# MIRA050CSP-Sheet1.net
KiCad netlist of a schematic drawn in Altium Designer
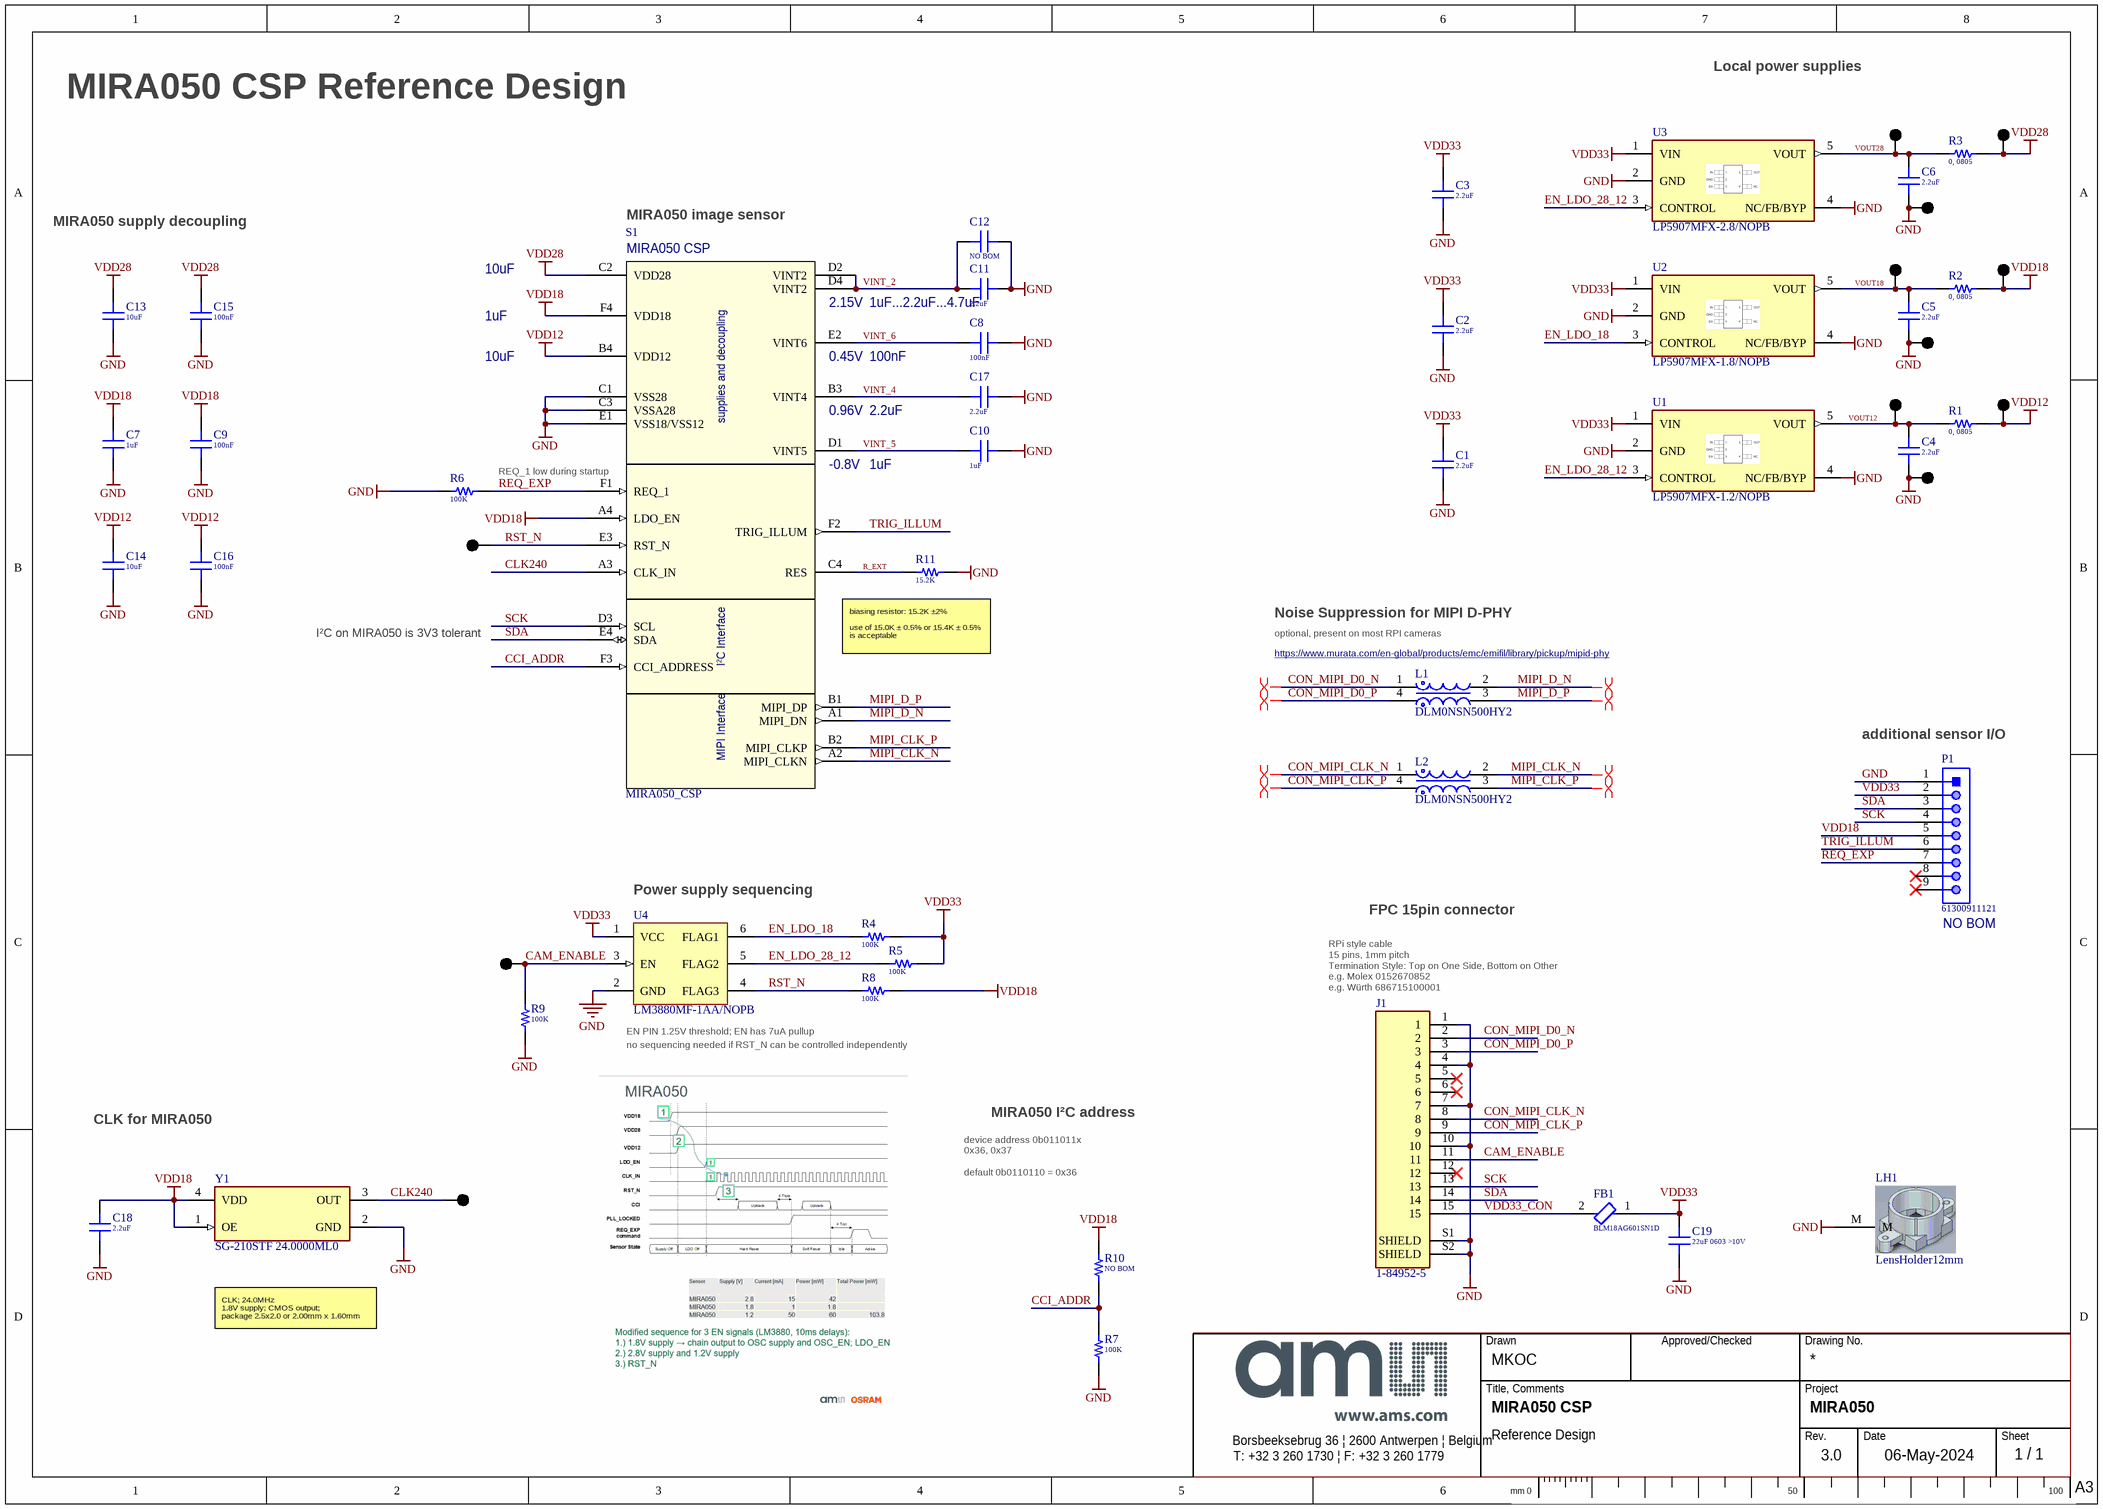
[diagram p0: MIRA050CSP-Sheet1.SchDoc]

(export (version "E")
  (design (tool "Eeschema 10.0.6"))
  (components
    (comp (ref "C1")
      (value "2.2uF")
      (footprint "CAPC0402_BEMA")
      (description "SMT Capacitor")
      (fields (field (name "PART NUMBER") "GRM155R61E225ME15D"))
      (libsource (lib "passives") (part "Capacitor"))
    )
    (comp (ref "C2")
      (value "2.2uF")
      (footprint "CAPC0402_BEMA")
      (description "SMT Capacitor")
      (fields (field (name "PART NUMBER") "GRM155R61E225ME15D"))
      (libsource (lib "passives") (part "Capacitor"))
    )
    (comp (ref "C3")
      (value "2.2uF")
      (footprint "CAPC0402_BEMA")
      (description "SMT Capacitor")
      (fields (field (name "PART NUMBER") "GRM155R61E225ME15D"))
      (libsource (lib "passives") (part "Capacitor"))
    )
    (comp (ref "C4")
      (value "2.2uF")
      (footprint "CAPC0402_BEMA")
      (description "SMT Capacitor")
      (fields (field (name "PART NUMBER") "GRM155R61E225ME15D"))
      (libsource (lib "passives") (part "Capacitor"))
    )
    (comp (ref "C5")
      (value "2.2uF")
      (footprint "CAPC0402_BEMA")
      (description "SMT Capacitor")
      (fields (field (name "PART NUMBER") "GRM155R61E225ME15D"))
      (libsource (lib "passives") (part "Capacitor"))
    )
    (comp (ref "C6")
      (value "2.2uF")
      (footprint "CAPC0402_BEMA")
      (description "SMT Capacitor")
      (fields (field (name "PART NUMBER") "GRM155R61E225ME15D"))
      (libsource (lib "passives") (part "Capacitor"))
    )
    (comp (ref "C7")
      (value "1uF")
      (footprint "CAPC0402_BEMA")
      (description "SMT Capacitor")
      (fields (field (name "PART NUMBER") "GRM155Z71A105KE01"))
      (libsource (lib "passives") (part "Capacitor"))
    )
    (comp (ref "C8")
      (value "100nF")
      (footprint "CAPC0402_BEMA")
      (description "SMT Capacitor")
      (fields (field (name "PART NUMBER") "GRM155R71E104KE14J"))
      (libsource (lib "passives") (part "Capacitor"))
    )
    (comp (ref "C9")
      (value "100nF")
      (footprint "CAPC0402_BEMA")
      (description "SMT Capacitor")
      (fields (field (name "PART NUMBER") "GRM155R71E104KE14J"))
      (libsource (lib "passives") (part "Capacitor"))
    )
    (comp (ref "C10")
      (value "1uF")
      (footprint "CAPC0402_BEMA")
      (description "SMT Capacitor")
      (fields (field (name "PART NUMBER") "GRM155Z71A105KE01"))
      (libsource (lib "passives") (part "Capacitor"))
    )
    (comp (ref "C11")
      (value "2.2uF")
      (footprint "CAPC0402_N")
      (description "SMT Capacitor")
      (fields (field (name "PART NUMBER") "GRM155R61E225ME15D"))
      (libsource (lib "passives") (part "Capacitor"))
    )
    (comp (ref "C12")
      (value "NO BOM")
      (footprint "CAPC0402_N")
      (description "SMT Capacitor")
      (libsource (lib "passives") (part "Capacitor"))
    )
    (comp (ref "C13")
      (value "10uF")
      (footprint "CAPC0402_BEMA")
      (description "SMT Capacitor")
      (fields (field (name "PART NUMBER") "GRM155R60J106ME15D"))
      (libsource (lib "passives") (part "Capacitor"))
    )
    (comp (ref "C14")
      (value "10uF")
      (footprint "CAPC0402_BEMA")
      (description "SMT Capacitor")
      (fields (field (name "PART NUMBER") "GRM155R60J106ME15D"))
      (libsource (lib "passives") (part "Capacitor"))
    )
    (comp (ref "C15")
      (value "100nF")
      (footprint "CAPC0402_BEMA")
      (description "SMT Capacitor")
      (fields (field (name "PART NUMBER") "GRM155R71E104KE14J"))
      (libsource (lib "passives") (part "Capacitor"))
    )
    (comp (ref "C16")
      (value "100nF")
      (footprint "CAPC0402_BEMA")
      (description "SMT Capacitor")
      (fields (field (name "PART NUMBER") "GRM155R71E104KE14J"))
      (libsource (lib "passives") (part "Capacitor"))
    )
    (comp (ref "C17")
      (value "2.2uF")
      (footprint "CAPC0402_BEMA")
      (description "SMT Capacitor")
      (fields (field (name "PART NUMBER") "GRM155R61E225ME15D"))
      (libsource (lib "passives") (part "Capacitor"))
    )
    (comp (ref "C18")
      (value "2.2uF")
      (footprint "CAPC0402_BEMA")
      (description "SMT Capacitor")
      (fields (field (name "PART NUMBER") "GRM155R61E225ME15D"))
      (libsource (lib "passives") (part "Capacitor"))
    )
    (comp (ref "C19")
      (value "22uF 0603 >10V")
      (footprint "CAPC0603_BEMA")
      (description "SMT Capacitor")
      (fields (field (name "PART NUMBER") "GRM187R61A226ME15D"))
      (libsource (lib "passives") (part "Capacitor"))
    )
    (comp (ref "FB1")
      (value "BLM18AG601SN1D")
      (footprint "FP-BLM18-0_15-t0_8-IPC_B")
      (description "Chip Ferrite Bead, 0603, 600Ω @ 100MHz, 0.38Ω, 25%, 500mA")
      (fields (field (name "TOLERANCE") "25%"))
      (libsource (lib "MIRA050CSP") (part "CMP-0686-00436-3"))
    )
    (comp (ref "J1")
      (value "1-84952-5")
      (footprint "TE_1-84952-5")
      (description "Conn FPC Connector SKT 15 POS 1mm Solder RA SMD T/R")
      (libsource (lib "MIRA220CSP") (part "1-84952-5"))
    )
    (comp (ref "L1")
      (value "DLM0NSN500HY2")
      (footprint "FP-DLM0N-MFG")
      (description "Common Mode Choke 50Ohm 100mA 4-Pin 03025 Paper T/R")
      (fields
        (field (name "MANUFACTURER") "Murata")
        (field (name "MANUFACTURER PART NUMBER") "DLM0NSN500HY2D")
      )
      (libsource (lib "MIRA050CSP") (part "CMP-2000-06161-2_1"))
    )
    (comp (ref "L2")
      (value "DLM0NSN500HY2")
      (footprint "FP-DLM0N-MFG")
      (description "Common Mode Choke 50Ohm 100mA 4-Pin 03025 Paper T/R")
      (fields
        (field (name "MANUFACTURER") "Murata")
        (field (name "MANUFACTURER PART NUMBER") "DLM0NSN500HY2D")
      )
      (libsource (lib "MIRA050CSP") (part "CMP-2000-06161-2_1"))
    )
    (comp (ref "LH1")
      (value "LensHolder12mm")
      (footprint "LensHolder12mmSmount")
      (libsource (lib "misc_components") (part "LensHolder12mm"))
    )
    (comp (ref "P1")
      (value "61300911121")
      (footprint "61300911121")
      (description "THT Vertical Pin Header WR-PHD, Pitch 2.54 mm, Single Row, 9 pins")
      (fields (field (name "MANUFACTURER") "Wurth Elektronik") (field (name "PUBLISHER") "WurthElektronik"))
      (libsource (lib "MIRA050CSP") (part "CMP-1502-01080-1"))
    )
    (comp (ref "R1")
      (value "0, 0805")
      (footprint "RESC0805_BEMA")
      (description "SMT Resistor")
      (fields (field (name "PART NUMBER") "0, 0805, generic"))
      (libsource (lib "passives") (part "Resistor"))
    )
    (comp (ref "R2")
      (value "0, 0805")
      (footprint "RESC0805_BEMA")
      (description "SMT Resistor")
      (fields (field (name "PART NUMBER") "0, 0805, generic"))
      (libsource (lib "passives") (part "Resistor"))
    )
    (comp (ref "R3")
      (value "0, 0805")
      (footprint "RESC0805_BEMA")
      (description "SMT Resistor")
      (fields (field (name "PART NUMBER") "0, 0805, generic"))
      (libsource (lib "passives") (part "Resistor"))
    )
    (comp (ref "R4")
      (value "100K")
      (footprint "RESC0402_BEMA")
      (description "SMT Resistor")
      (fields (field (name "PART NUMBER") "100K 0402, generic"))
      (libsource (lib "passives") (part "Resistor"))
    )
    (comp (ref "R5")
      (value "100K")
      (footprint "RESC0402_BEMA")
      (description "SMT Resistor")
      (fields (field (name "PART NUMBER") "100K 0402, generic"))
      (libsource (lib "passives") (part "Resistor"))
    )
    (comp (ref "R6")
      (value "100K")
      (footprint "RESC0402_BEMA")
      (description "SMT Resistor")
      (fields (field (name "PART NUMBER") "100K 0402, generic"))
      (libsource (lib "passives") (part "Resistor"))
    )
    (comp (ref "R7")
      (value "100K")
      (footprint "RESC0402_BEMA")
      (description "SMT Resistor")
      (fields (field (name "PART NUMBER") "100K 0402, generic"))
      (libsource (lib "passives") (part "Resistor"))
    )
    (comp (ref "R8")
      (value "100K")
      (footprint "RESC0402_BEMA")
      (description "SMT Resistor")
      (fields (field (name "PART NUMBER") "100K 0402, generic"))
      (libsource (lib "passives") (part "Resistor"))
    )
    (comp (ref "R9")
      (value "100K")
      (footprint "RESC0402_BEMA")
      (description "SMT Resistor")
      (fields (field (name "PART NUMBER") "100K 0402, generic"))
      (libsource (lib "passives") (part "Resistor"))
    )
    (comp (ref "R10")
      (value "NO BOM")
      (footprint "RESC0402_BEMA")
      (description "SMT Resistor")
      (libsource (lib "passives") (part "Resistor"))
    )
    (comp (ref "R11")
      (value "15.2K")
      (footprint "RESC0402_BEMA")
      (description "SMT Resistor")
      (fields (field (name "PART NUMBER") "RN73R1ETTP1522B25"))
      (libsource (lib "passives") (part "Resistor"))
    )
    (comp (ref "S1")
      (value "MIRA050_CSP")
      (footprint "MIRA050CSP:MIRA050CSP")
      (description "AMS-OSRAM MIRA050 CSP, MONO")
      (fields (field (name "PART NUMBER") "Mira050-2QM1WB"))
      (libsource (lib "MIRA050CSP") (part "MIRA050_CSP"))
    )
    (comp (ref "TP1")
      (value "1V8")
      (footprint "misc_components:TP_1mm")
      (description "Test Point, various footprints")
      (libsource (lib "misc_components") (part "TestPoint"))
    )
    (comp (ref "TP2")
      (value "1V2")
      (footprint "misc_components:TP_1mm")
      (description "Test Point, various footprints")
      (libsource (lib "misc_components") (part "TestPoint"))
    )
    (comp (ref "TP3")
      (value "TestPoint")
      (footprint "misc_components:TP_1mm")
      (description "Test Point, various footprints")
      (libsource (lib "misc_components") (part "TestPoint"))
    )
    (comp (ref "TP4")
      (value "TestPoint")
      (footprint "misc_components:TP_1mm")
      (description "Test Point, various footprints")
      (libsource (lib "misc_components") (part "TestPoint"))
    )
    (comp (ref "TP5")
      (value "2V8")
      (footprint "misc_components:TP_1mm")
      (description "Test Point, various footprints")
      (libsource (lib "misc_components") (part "TestPoint"))
    )
    (comp (ref "TP6")
      (value "TestPoint")
      (footprint "misc_components:TP_1mm")
      (description "Test Point, various footprints")
      (libsource (lib "misc_components") (part "TestPoint"))
    )
    (comp (ref "TP7")
      (value "TestPoint")
      (footprint "misc_components:TP_075mm")
      (description "Test Point, various footprints")
      (libsource (lib "misc_components") (part "TestPoint"))
    )
    (comp (ref "TP8")
      (value "TestPoint")
      (footprint "misc_components:TP_075mm")
      (description "Test Point, various footprints")
      (libsource (lib "misc_components") (part "TestPoint"))
    )
    (comp (ref "TP9")
      (value "TestPoint")
      (footprint "misc_components:TP_075mm")
      (description "Test Point, various footprints")
      (libsource (lib "misc_components") (part "TestPoint"))
    )
    (comp (ref "TP10")
      (value "TestPoint")
      (footprint "TP_1mm")
      (description "Test Point, various footprints")
      (libsource (lib "MIRA050CSP") (part "5001"))
    )
    (comp (ref "TP11")
      (value "TestPoint")
      (footprint "TP_1mm")
      (description "Test Point, various footprints")
      (libsource (lib "MIRA050CSP") (part "5001"))
    )
    (comp (ref "TP12")
      (value "TestPoint")
      (footprint "TP_1mm")
      (description "Test Point, various footprints")
      (libsource (lib "MIRA050CSP") (part "5001"))
    )
    (comp (ref "U1")
      (value "LP5907MFX-1.2/NOPB")
      (footprint "misc_components:FP-DBV0005A-MFG")
      (description "IC REG LINEAR fixed Voltage, SOT23-5 / SOT-25 / SC74A package")
      (libsource (lib "misc_components") (part "LDO-STO23-5"))
    )
    (comp (ref "U2")
      (value "LP5907MFX-1.8/NOPB")
      (footprint "misc_components:FP-DBV0005A-MFG")
      (description "IC REG LINEAR fixed Voltage, SOT23-5 / SOT-25 / SC74A package")
      (libsource (lib "misc_components") (part "LDO-STO23-5"))
    )
    (comp (ref "U3")
      (value "LP5907MFX-2.8/NOPB")
      (footprint "misc_components:FP-DBV0005A-MFG")
      (description "IC REG LINEAR fixed Voltage, SOT23-5 / SOT-25 / SC74A package")
      (libsource (lib "misc_components") (part "LDO-STO23-5"))
    )
    (comp (ref "U4")
      (value "LM3880MF-1AA/NOPB")
      (footprint "DBV0006A_N")
      (description "Power Sequencer, 6-pin SOT-23, Pb-Free, 1000 Reel")
      (libsource (lib "MIRA050CSP") (part "CMP-0063-01015-4"))
    )
    (comp (ref "Y1")
      (value "SG-210STF 24.0000ML0")
      (footprint "MIRA050CSP:2.5x2_OSC")
      (description "OSC, 24MHz, 1.8V, CMOS, EN")
      (libsource (lib "MIRA050CSP") (part "OSC"))
    )
  )
  (nets
    (net (code "1") (name "/CAM_ENABLE") (class "Default")
      (node (ref "J1") (pin "11") (pinfunction "11_11") (pintype "passive"))
      (node (ref "R9") (pin "2") (pinfunction "2_2") (pintype "passive"))
      (node (ref "TP12") (pin "1") (pintype "passive"))
      (node (ref "U4") (pin "3") (pinfunction "EN_3") (pintype "input"))
    )
    (net (code "2") (name "/CCI_ADDR") (class "Default")
      (node (ref "R10") (pin "1") (pinfunction "1_1") (pintype "passive"))
      (node (ref "R7") (pin "2") (pinfunction "2_2") (pintype "passive"))
      (node (ref "S1") (pin "F3") (pinfunction "CCI_ADDRESS_F3") (pintype "input"))
    )
    (net (code "3") (name "/CLK240") (class "Default")
      (node (ref "S1") (pin "A3") (pinfunction "CLK_IN_A3") (pintype "input"))
      (node (ref "TP11") (pin "1") (pintype "passive"))
      (node (ref "Y1") (pin "3") (pinfunction "OUT_3") (pintype "passive"))
    )
    (net (code "4") (name "/CON_MIPI_CLK_N") (class "Default")
      (node (ref "J1") (pin "8") (pinfunction "8_8") (pintype "passive"))
      (node (ref "L2") (pin "1") (pinfunction "1_1") (pintype "passive"))
    )
    (net (code "5") (name "/CON_MIPI_CLK_P") (class "Default")
      (node (ref "J1") (pin "9") (pinfunction "9_9") (pintype "passive"))
      (node (ref "L2") (pin "4") (pinfunction "4_4") (pintype "passive"))
    )
    (net (code "6") (name "/CON_MIPI_D0_N") (class "Default")
      (node (ref "J1") (pin "2") (pinfunction "2_2") (pintype "passive"))
      (node (ref "L1") (pin "1") (pinfunction "1_1") (pintype "passive"))
    )
    (net (code "7") (name "/CON_MIPI_D0_P") (class "Default")
      (node (ref "J1") (pin "3") (pinfunction "3_3") (pintype "passive"))
      (node (ref "L1") (pin "4") (pinfunction "4_4") (pintype "passive"))
    )
    (net (code "8") (name "/EN_LDO_18") (class "Default")
      (node (ref "R4") (pin "1") (pinfunction "1_1") (pintype "passive"))
      (node (ref "U2") (pin "3") (pinfunction "CONTROL_3") (pintype "input"))
      (node (ref "U4") (pin "6") (pinfunction "FLAG1_6") (pintype "open_collector"))
    )
    (net (code "9") (name "/EN_LDO_28_12") (class "Default")
      (node (ref "R5") (pin "1") (pinfunction "1_1") (pintype "passive"))
      (node (ref "U1") (pin "3") (pinfunction "CONTROL_3") (pintype "input"))
      (node (ref "U3") (pin "3") (pinfunction "CONTROL_3") (pintype "input"))
      (node (ref "U4") (pin "5") (pinfunction "FLAG2_5") (pintype "open_collector"))
    )
    (net (code "10") (name "/MIPI_CLK_N") (class "Default")
      (node (ref "L2") (pin "2") (pinfunction "2_2") (pintype "passive"))
      (node (ref "S1") (pin "A2") (pinfunction "MIPI_CLKN_A2") (pintype "output"))
    )
    (net (code "11") (name "/MIPI_CLK_P") (class "Default")
      (node (ref "L2") (pin "3") (pinfunction "3_3") (pintype "passive"))
      (node (ref "S1") (pin "B2") (pinfunction "MIPI_CLKP_B2") (pintype "output"))
    )
    (net (code "12") (name "/MIPI_D_N") (class "Default")
      (node (ref "L1") (pin "2") (pinfunction "2_2") (pintype "passive"))
      (node (ref "S1") (pin "A1") (pinfunction "MIPI_DN_A1") (pintype "output"))
    )
    (net (code "13") (name "/MIPI_D_P") (class "Default")
      (node (ref "L1") (pin "3") (pinfunction "3_3") (pintype "passive"))
      (node (ref "S1") (pin "B1") (pinfunction "MIPI_DP_B1") (pintype "output"))
    )
    (net (code "14") (name "/REQ_EXP") (class "Default")
      (node (ref "P1") (pin "7") (pinfunction "7_7") (pintype "passive"))
      (node (ref "R6") (pin "2") (pinfunction "2_2") (pintype "passive"))
      (node (ref "S1") (pin "F1") (pinfunction "REQ_1_F1") (pintype "input"))
    )
    (net (code "15") (name "/RST_N") (class "Default")
      (node (ref "R8") (pin "1") (pinfunction "1_1") (pintype "passive"))
      (node (ref "S1") (pin "E3") (pinfunction "RST_N_E3") (pintype "input"))
      (node (ref "TP10") (pin "1") (pintype "passive"))
      (node (ref "U4") (pin "4") (pinfunction "FLAG3_4") (pintype "open_collector"))
    )
    (net (code "16") (name "/R_EXT") (class "Default")
      (node (ref "R11") (pin "1") (pinfunction "1_1") (pintype "passive"))
      (node (ref "S1") (pin "C4") (pinfunction "RES_C4") (pintype "passive"))
    )
    (net (code "17") (name "/SCK") (class "Default")
      (node (ref "J1") (pin "13") (pinfunction "13_13") (pintype "passive"))
      (node (ref "P1") (pin "4") (pinfunction "4_4") (pintype "passive"))
      (node (ref "S1") (pin "D3") (pinfunction "SCL_D3") (pintype "input"))
    )
    (net (code "18") (name "/SDA") (class "Default")
      (node (ref "J1") (pin "14") (pinfunction "14_14") (pintype "passive"))
      (node (ref "P1") (pin "3") (pinfunction "3_3") (pintype "passive"))
      (node (ref "S1") (pin "E4") (pinfunction "SDA_E4") (pintype "bidirectional"))
    )
    (net (code "19") (name "/TRIG_ILLUM") (class "Default")
      (node (ref "P1") (pin "6") (pinfunction "6_6") (pintype "passive"))
      (node (ref "S1") (pin "F2") (pinfunction "TRIG_ILLUM_F2") (pintype "output"))
    )
    (net (code "20") (name "/VDD33_CON") (class "Default")
      (node (ref "FB1") (pin "2") (pinfunction "2_2") (pintype "passive"))
      (node (ref "J1") (pin "15") (pinfunction "15_15") (pintype "passive"))
    )
    (net (code "21") (name "/VINT_2") (class "Default")
      (node (ref "C11") (pin "1") (pinfunction "1_1") (pintype "passive"))
      (node (ref "C12") (pin "1") (pinfunction "1_1") (pintype "passive"))
      (node (ref "S1") (pin "D2") (pinfunction "VINT2_D2") (pintype "passive"))
      (node (ref "S1") (pin "D4") (pinfunction "VINT2_D4") (pintype "passive"))
    )
    (net (code "22") (name "/VINT_4") (class "Default")
      (node (ref "C17") (pin "1") (pinfunction "1_1") (pintype "passive"))
      (node (ref "S1") (pin "B3") (pinfunction "VINT4_B3") (pintype "passive"))
    )
    (net (code "23") (name "/VINT_5") (class "Default")
      (node (ref "C10") (pin "1") (pinfunction "1_1") (pintype "passive"))
      (node (ref "S1") (pin "D1") (pinfunction "VINT5_D1") (pintype "passive"))
    )
    (net (code "24") (name "/VINT_6") (class "Default")
      (node (ref "C8") (pin "1") (pinfunction "1_1") (pintype "passive"))
      (node (ref "S1") (pin "E2") (pinfunction "VINT6_E2") (pintype "passive"))
    )
    (net (code "25") (name "/VOUT12") (class "Default")
      (node (ref "C4") (pin "1") (pinfunction "1_1") (pintype "passive"))
      (node (ref "R1") (pin "1") (pinfunction "1_1") (pintype "passive"))
      (node (ref "TP3") (pin "1") (pintype "passive"))
      (node (ref "U1") (pin "5") (pinfunction "VOUT_5") (pintype "output"))
    )
    (net (code "26") (name "/VOUT18") (class "Default")
      (node (ref "C5") (pin "1") (pinfunction "1_1") (pintype "passive"))
      (node (ref "R2") (pin "1") (pinfunction "1_1") (pintype "passive"))
      (node (ref "TP4") (pin "1") (pintype "passive"))
      (node (ref "U2") (pin "5") (pinfunction "VOUT_5") (pintype "output"))
    )
    (net (code "27") (name "/VOUT28") (class "Default")
      (node (ref "C6") (pin "1") (pinfunction "1_1") (pintype "passive"))
      (node (ref "R3") (pin "1") (pinfunction "1_1") (pintype "passive"))
      (node (ref "TP6") (pin "1") (pintype "passive"))
      (node (ref "U3") (pin "5") (pinfunction "VOUT_5") (pintype "output"))
    )
    (net (code "28") (name "GND") (class "Default")
      (node (ref "C1") (pin "2") (pinfunction "2_2") (pintype "passive"))
      (node (ref "C10") (pin "2") (pinfunction "2_2") (pintype "passive"))
      (node (ref "C11") (pin "2") (pinfunction "2_2") (pintype "passive"))
      (node (ref "C12") (pin "2") (pinfunction "2_2") (pintype "passive"))
      (node (ref "C13") (pin "2") (pinfunction "2_2") (pintype "passive"))
      (node (ref "C14") (pin "2") (pinfunction "2_2") (pintype "passive"))
      (node (ref "C15") (pin "2") (pinfunction "2_2") (pintype "passive"))
      (node (ref "C16") (pin "2") (pinfunction "2_2") (pintype "passive"))
      (node (ref "C17") (pin "2") (pinfunction "2_2") (pintype "passive"))
      (node (ref "C18") (pin "2") (pinfunction "2_2") (pintype "passive"))
      (node (ref "C19") (pin "2") (pinfunction "2_2") (pintype "passive"))
      (node (ref "C2") (pin "2") (pinfunction "2_2") (pintype "passive"))
      (node (ref "C3") (pin "2") (pinfunction "2_2") (pintype "passive"))
      (node (ref "C4") (pin "2") (pinfunction "2_2") (pintype "passive"))
      (node (ref "C5") (pin "2") (pinfunction "2_2") (pintype "passive"))
      (node (ref "C6") (pin "2") (pinfunction "2_2") (pintype "passive"))
      (node (ref "C7") (pin "2") (pinfunction "2_2") (pintype "passive"))
      (node (ref "C8") (pin "2") (pinfunction "2_2") (pintype "passive"))
      (node (ref "C9") (pin "2") (pinfunction "2_2") (pintype "passive"))
      (node (ref "J1") (pin "1") (pinfunction "1_1") (pintype "passive"))
      (node (ref "J1") (pin "10") (pinfunction "10_10") (pintype "passive"))
      (node (ref "J1") (pin "4") (pinfunction "4_4") (pintype "passive"))
      (node (ref "J1") (pin "7") (pinfunction "7_7") (pintype "passive"))
      (node (ref "J1") (pin "S1") (pinfunction "SHIELD_S1") (pintype "passive"))
      (node (ref "J1") (pin "S2") (pinfunction "SHIELD_S2") (pintype "passive"))
      (node (ref "LH1") (pin "M") (pinfunction "M_M") (pintype "passive"))
      (node (ref "P1") (pin "1") (pinfunction "1_1") (pintype "passive"))
      (node (ref "R11") (pin "2") (pinfunction "2_2") (pintype "passive"))
      (node (ref "R6") (pin "1") (pinfunction "1_1") (pintype "passive"))
      (node (ref "R7") (pin "1") (pinfunction "1_1") (pintype "passive"))
      (node (ref "R9") (pin "1") (pinfunction "1_1") (pintype "passive"))
      (node (ref "S1") (pin "C1") (pinfunction "VSS28_C1") (pintype "power_in"))
      (node (ref "S1") (pin "C3") (pinfunction "VSSA28_C3") (pintype "power_in"))
      (node (ref "S1") (pin "E1") (pinfunction "VSS18/VSS12_E1") (pintype "power_in"))
      (node (ref "TP7") (pin "1") (pintype "passive"))
      (node (ref "TP8") (pin "1") (pintype "passive"))
      (node (ref "TP9") (pin "1") (pintype "passive"))
      (node (ref "U1") (pin "2") (pinfunction "GND_2") (pintype "power_in"))
      (node (ref "U1") (pin "4") (pinfunction "NC/FB/BYP_4") (pintype "passive"))
      (node (ref "U2") (pin "2") (pinfunction "GND_2") (pintype "power_in"))
      (node (ref "U2") (pin "4") (pinfunction "NC/FB/BYP_4") (pintype "passive"))
      (node (ref "U3") (pin "2") (pinfunction "GND_2") (pintype "power_in"))
      (node (ref "U3") (pin "4") (pinfunction "NC/FB/BYP_4") (pintype "passive"))
      (node (ref "U4") (pin "2") (pinfunction "GND_2") (pintype "power_in"))
      (node (ref "Y1") (pin "2") (pinfunction "GND_2") (pintype "power_in"))
    )
    (net (code "29") (name "VDD12") (class "Default")
      (node (ref "C14") (pin "1") (pinfunction "1_1") (pintype "passive"))
      (node (ref "C16") (pin "1") (pinfunction "1_1") (pintype "passive"))
      (node (ref "R1") (pin "2") (pinfunction "2_2") (pintype "passive"))
      (node (ref "S1") (pin "B4") (pinfunction "VDD12_B4") (pintype "power_in"))
      (node (ref "TP2") (pin "1") (pintype "passive"))
    )
    (net (code "30") (name "VDD18") (class "Default")
      (node (ref "C18") (pin "1") (pinfunction "1_1") (pintype "passive"))
      (node (ref "C7") (pin "1") (pinfunction "1_1") (pintype "passive"))
      (node (ref "C9") (pin "1") (pinfunction "1_1") (pintype "passive"))
      (node (ref "P1") (pin "5") (pinfunction "5_5") (pintype "passive"))
      (node (ref "R10") (pin "2") (pinfunction "2_2") (pintype "passive"))
      (node (ref "R2") (pin "2") (pinfunction "2_2") (pintype "passive"))
      (node (ref "R8") (pin "2") (pinfunction "2_2") (pintype "passive"))
      (node (ref "S1") (pin "A4") (pinfunction "LDO_EN_A4") (pintype "input"))
      (node (ref "S1") (pin "F4") (pinfunction "VDD18_F4") (pintype "power_in"))
      (node (ref "TP1") (pin "1") (pintype "passive"))
      (node (ref "Y1") (pin "1") (pinfunction "OE_1") (pintype "input"))
      (node (ref "Y1") (pin "4") (pinfunction "VDD_4") (pintype "power_in"))
    )
    (net (code "31") (name "VDD28") (class "Default")
      (node (ref "C13") (pin "1") (pinfunction "1_1") (pintype "passive"))
      (node (ref "C15") (pin "1") (pinfunction "1_1") (pintype "passive"))
      (node (ref "R3") (pin "2") (pinfunction "2_2") (pintype "passive"))
      (node (ref "S1") (pin "C2") (pinfunction "VDD28_C2") (pintype "power_in"))
      (node (ref "TP5") (pin "1") (pintype "passive"))
    )
    (net (code "32") (name "VDD33") (class "Default")
      (node (ref "C1") (pin "1") (pinfunction "1_1") (pintype "passive"))
      (node (ref "C19") (pin "1") (pinfunction "1_1") (pintype "passive"))
      (node (ref "C2") (pin "1") (pinfunction "1_1") (pintype "passive"))
      (node (ref "C3") (pin "1") (pinfunction "1_1") (pintype "passive"))
      (node (ref "FB1") (pin "1") (pinfunction "1_1") (pintype "passive"))
      (node (ref "P1") (pin "2") (pinfunction "2_2") (pintype "passive"))
      (node (ref "R4") (pin "2") (pinfunction "2_2") (pintype "passive"))
      (node (ref "R5") (pin "2") (pinfunction "2_2") (pintype "passive"))
      (node (ref "U1") (pin "1") (pinfunction "VIN_1") (pintype "power_in"))
      (node (ref "U2") (pin "1") (pinfunction "VIN_1") (pintype "power_in"))
      (node (ref "U3") (pin "1") (pinfunction "VIN_1") (pintype "power_in"))
      (node (ref "U4") (pin "1") (pinfunction "VCC_1") (pintype "power_in"))
    )
    (net (code "33") (name "unconnected-(J1-Pad5)") (class "Default")
      (node (ref "J1") (pin "5") (pinfunction "5_5") (pintype "passive+no_connect"))
    )
    (net (code "34") (name "unconnected-(J1-Pad6)") (class "Default")
      (node (ref "J1") (pin "6") (pinfunction "6_6") (pintype "passive+no_connect"))
    )
    (net (code "35") (name "unconnected-(J1-Pad12)") (class "Default")
      (node (ref "J1") (pin "12") (pinfunction "12_12") (pintype "passive+no_connect"))
    )
    (net (code "36") (name "unconnected-(P1-Pad8)") (class "Default")
      (node (ref "P1") (pin "8") (pinfunction "8_8") (pintype "passive+no_connect"))
    )
    (net (code "37") (name "unconnected-(P1-Pad9)") (class "Default")
      (node (ref "P1") (pin "9") (pinfunction "9_9") (pintype "passive+no_connect"))
    )
  )
)
